# TOP.net
KiCad netlist of a schematic drawn in Altium Designer
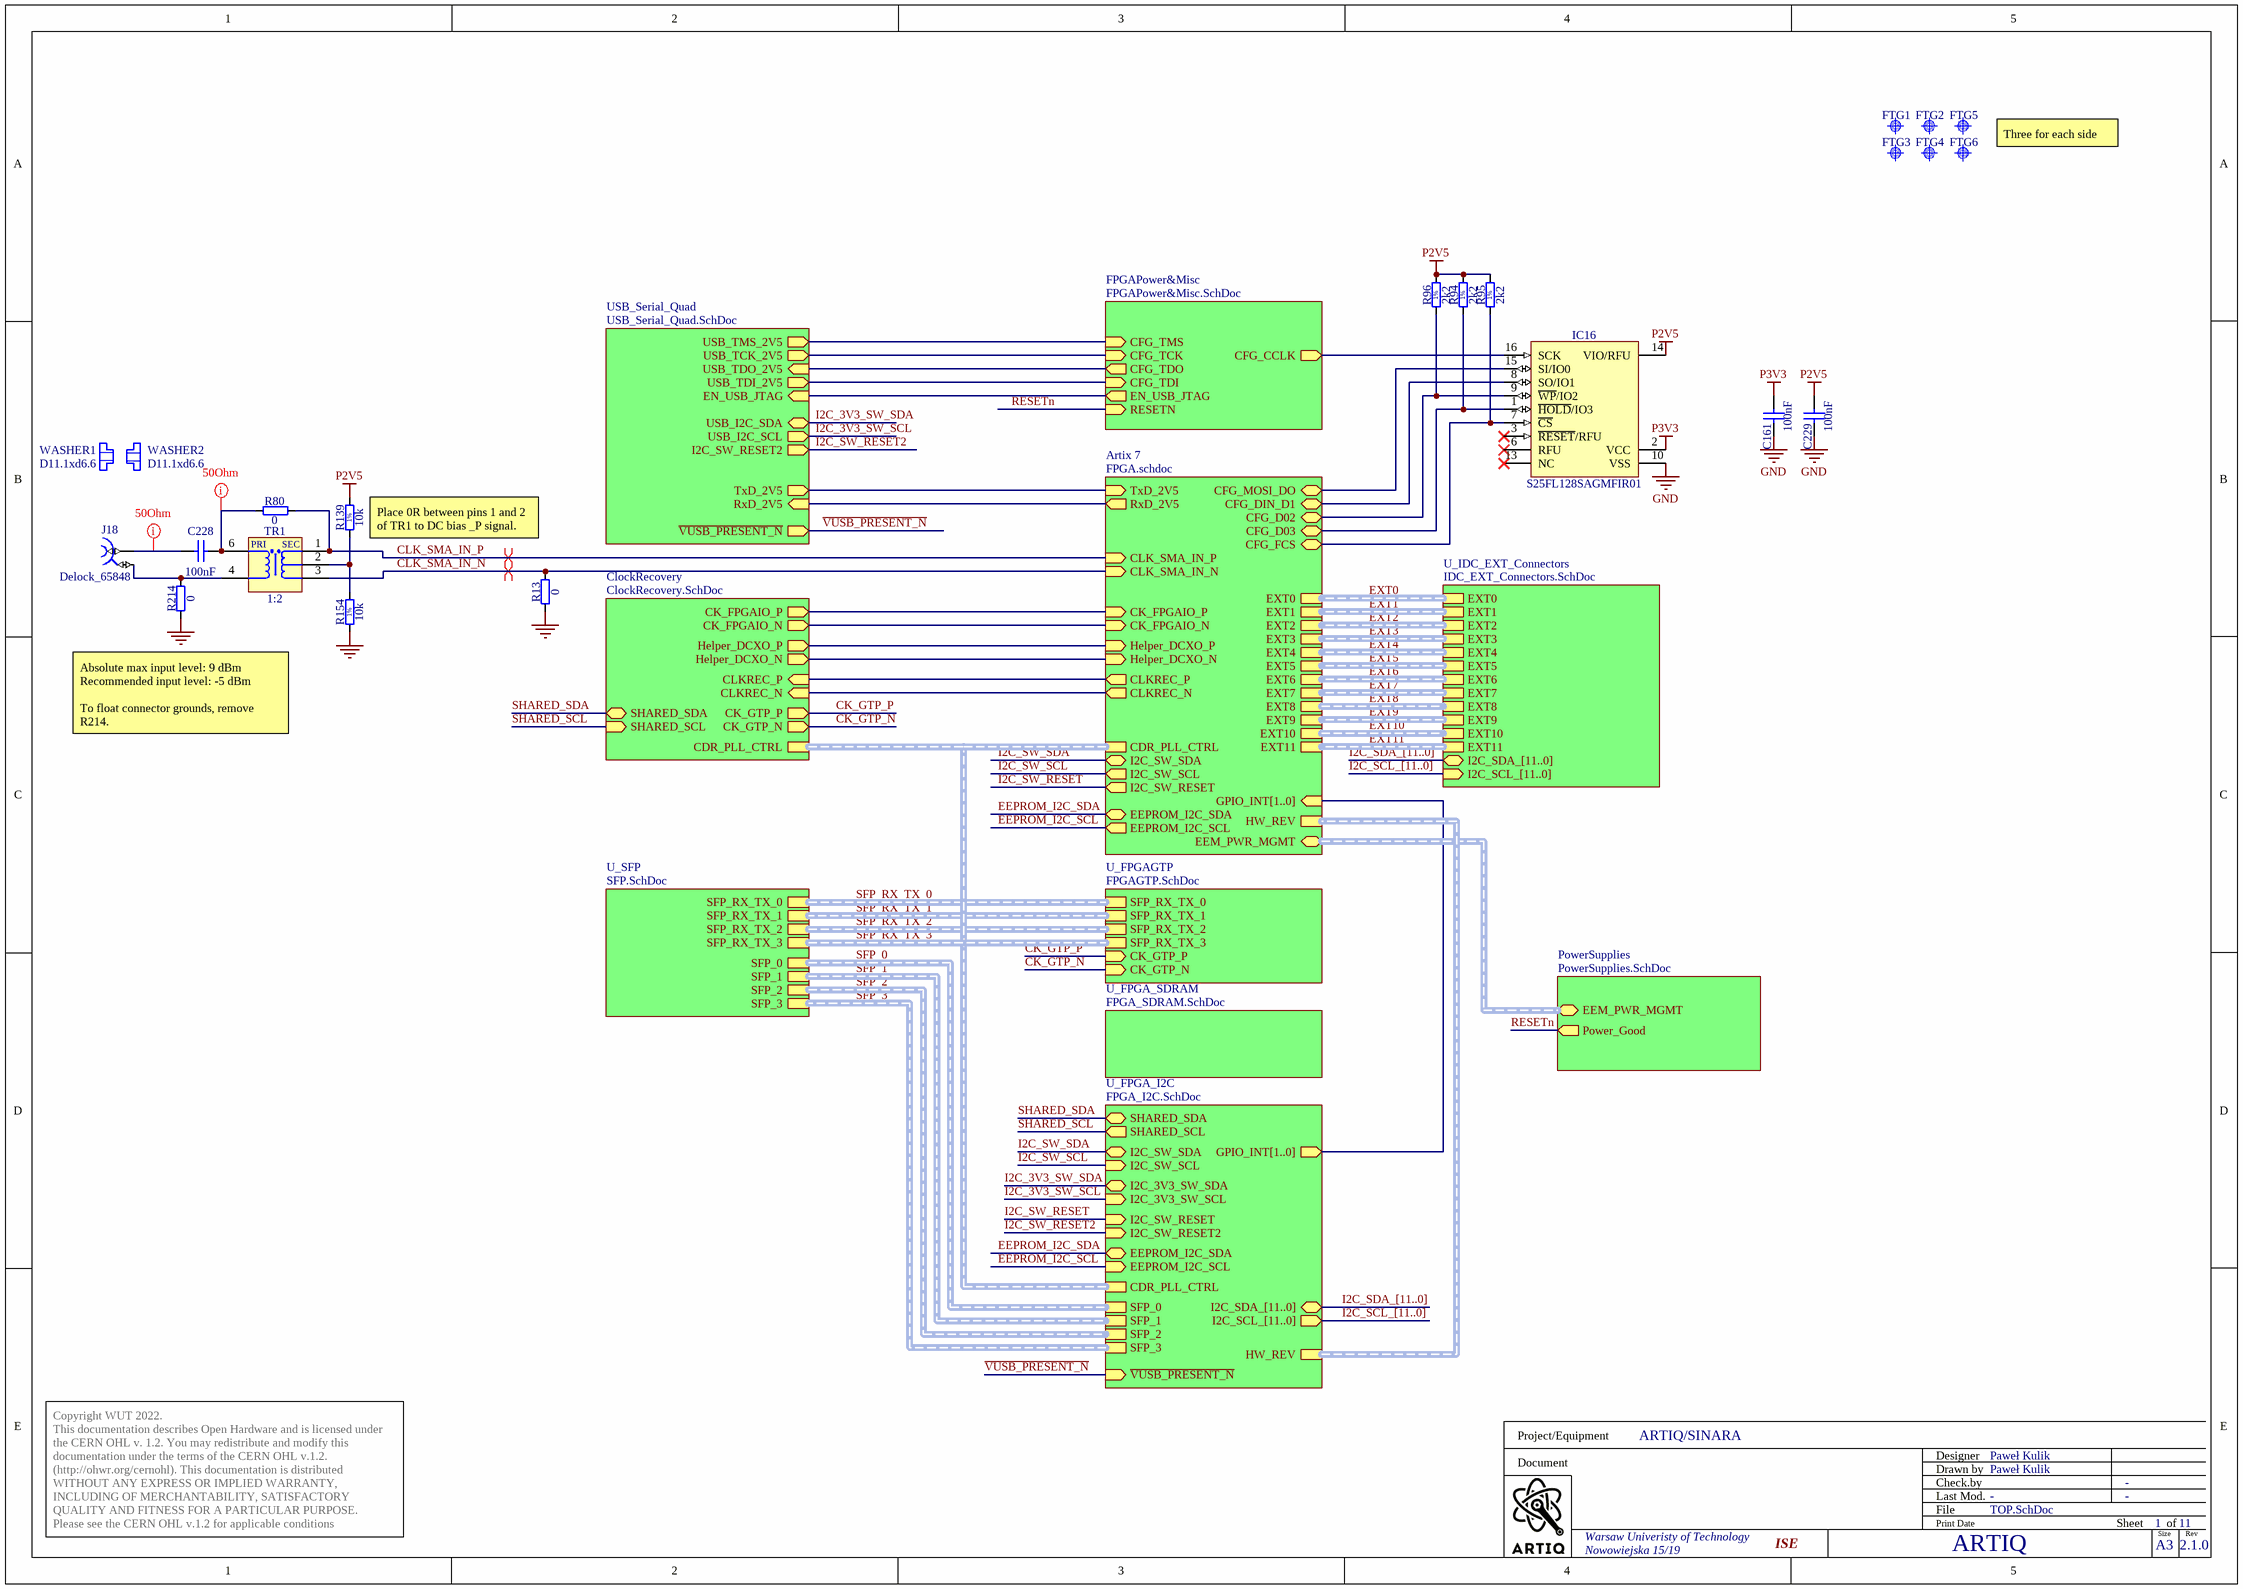
[diagram p0: TOP.SchDoc]

(export (version "E")
  (design (tool "Eeschema 10.0.6"))
  (components
    (comp (ref "C161")
      (value "100nF")
      (footprint "CAPC0603X33N")
      (description "Non-polarised capacitor")
      (fields
        (field (name "PART NUMBER") "CC0201_100NF_6.3V_10%_X5R")
        (field (name "VOLTAGE") "6.3V")
        (field (name "AUTHOR") "CERN DEM JLC")
      )
      (libsource (lib "Capacitors") (part "Capacitor - non polarized"))
    )
    (comp (ref "C228")
      (value "100nF")
      (footprint "CAPC0603X33N")
      (description "Non-polarised capacitor")
      (fields
        (field (name "PART NUMBER") "CC0201_100NF_6.3V_10%_X5R")
        (field (name "VOLTAGE") "6.3V")
        (field (name "AUTHOR") "CERN DEM JLC")
      )
      (libsource (lib "Capacitors") (part "Capacitor - non polarized"))
    )
    (comp (ref "C229")
      (value "100nF")
      (footprint "CAPC0603X33N")
      (description "Non-polarised capacitor")
      (fields
        (field (name "PART NUMBER") "CC0201_100NF_6.3V_10%_X5R")
        (field (name "VOLTAGE") "6.3V")
        (field (name "AUTHOR") "CERN DEM JLC")
      )
      (libsource (lib "Capacitors") (part "Capacitor - non polarized"))
    )
    (comp (ref "FTG1")
      (value "Use only in PCB")
      (footprint "FIDUCIAL_TOP_C100-200")
      (description "Fiducial Target")
      (fields (field (name "PART NUMBER") "FIDUCIAL_TARGET_C100-200") (field (name "AUTHOR") "CERN DEM JLC"))
      (libsource (lib "Eletro-mechanical") (part "Fiducial Target"))
    )
    (comp (ref "FTG2")
      (value "Use only in PCB")
      (footprint "FIDUCIAL_TOP_S100-200")
      (description "Fiducial Target")
      (fields (field (name "PART NUMBER") "FIDUCIAL_TARGET_S100-200") (field (name "AUTHOR") "CERN DEM JLC"))
      (libsource (lib "Eletro-mechanical") (part "Fiducial Target"))
    )
    (comp (ref "FTG3")
      (value "Use only in PCB")
      (footprint "FIDUCIAL_TOP_C100-200")
      (description "Fiducial Target")
      (fields (field (name "PART NUMBER") "FIDUCIAL_TARGET_C100-200") (field (name "AUTHOR") "CERN DEM JLC"))
      (libsource (lib "Eletro-mechanical") (part "Fiducial Target"))
    )
    (comp (ref "FTG4")
      (value "Use only in PCB")
      (footprint "FIDUCIAL_TOP_C100-200")
      (description "Fiducial Target")
      (fields (field (name "PART NUMBER") "FIDUCIAL_TARGET_C100-200") (field (name "AUTHOR") "CERN DEM JLC"))
      (libsource (lib "Eletro-mechanical") (part "Fiducial Target"))
    )
    (comp (ref "FTG5")
      (value "Use only in PCB")
      (footprint "FIDUCIAL_TOP_C100-200")
      (description "Fiducial Target")
      (fields (field (name "PART NUMBER") "FIDUCIAL_TARGET_C100-200") (field (name "AUTHOR") "CERN DEM JLC"))
      (libsource (lib "Eletro-mechanical") (part "Fiducial Target"))
    )
    (comp (ref "FTG6")
      (value "Use only in PCB")
      (footprint "FIDUCIAL_TOP_S100-200")
      (description "Fiducial Target")
      (fields (field (name "PART NUMBER") "FIDUCIAL_TARGET_S100-200") (field (name "AUTHOR") "CERN DEM JLC"))
      (libsource (lib "Eletro-mechanical") (part "Fiducial Target"))
    )
    (comp (ref "IC16")
      (value "S25FL128SAGMFIR01")
      (footprint "SOIC127P1030X265-16N")
      (fields (field (name "MANUFACTURER") "SPANSION") (field (name "AUTHOR") "CERN DEM JLC"))
      (libsource (lib "ICs And Semiconductors") (part "S25FL128SAGMFIR01"))
    )
    (comp (ref "J18")
      (value "Delock_65848")
      (footprint "Delock_65848")
      (description "SMA connector Delock 65848")
      (libsource (lib "TechnoSystem Workspace") (part "Coax_1Female_1Shield"))
    )
    (comp (ref "R13")
      (value "0")
      (footprint "RESC1005X40N")
      (description "Resistor")
      (fields
        (field (name "PART NUMBER") "R0402_0R_JUMPER")
        (field (name "MANUFACTURER") "GENERIC")
        (field (name "AUTHOR") "CERN DEM JLC")
      )
      (libsource (lib "Resistors") (part "Resistor"))
    )
    (comp (ref "R80")
      (value "0")
      (footprint "RESC1005X40N")
      (description "Resistor")
      (fields
        (field (name "PART NUMBER") "R0402_0R_JUMPER")
        (field (name "MANUFACTURER") "GENERIC")
        (field (name "AUTHOR") "CERN DEM JLC")
      )
      (libsource (lib "Resistors") (part "Resistor"))
    )
    (comp (ref "R94")
      (value "2k2")
      (footprint "RESC1005X40N")
      (description "Resistor - 1%")
      (fields
        (field (name "PART NUMBER") "R0402_2K2_1%_0.0625W_100PPM")
        (field (name "POWER") "0.0625W")
        (field (name "AUTHOR") "CERN DEM JLC")
      )
      (libsource (lib "Resistors") (part "Resistor - 1%"))
    )
    (comp (ref "R95")
      (value "2k2")
      (footprint "RESC1005X40N")
      (description "Resistor - 1%")
      (fields
        (field (name "PART NUMBER") "R0402_2K2_1%_0.0625W_100PPM")
        (field (name "POWER") "0.0625W")
        (field (name "AUTHOR") "CERN DEM JLC")
      )
      (libsource (lib "Resistors") (part "Resistor - 1%"))
    )
    (comp (ref "R96")
      (value "2k2")
      (footprint "RESC1005X40N")
      (description "Resistor - 1%")
      (fields
        (field (name "PART NUMBER") "R0402_2K2_1%_0.0625W_100PPM")
        (field (name "POWER") "0.0625W")
        (field (name "AUTHOR") "CERN DEM JLC")
      )
      (libsource (lib "Resistors") (part "Resistor - 1%"))
    )
    (comp (ref "R139")
      (value "10k")
      (footprint "RESC1005X40N")
      (description "Resistor - 1%")
      (fields
        (field (name "PART NUMBER") "R0402_10K_1%_0.0625W_100PPM")
        (field (name "POWER") "0.0625W")
        (field (name "AUTHOR") "CERN DEM JLC")
      )
      (libsource (lib "Resistors") (part "Resistor - 1%"))
    )
    (comp (ref "R154")
      (value "10k")
      (footprint "RESC1005X40N")
      (description "Resistor - 1%")
      (fields
        (field (name "PART NUMBER") "R0402_10K_1%_0.0625W_100PPM")
        (field (name "POWER") "0.0625W")
        (field (name "AUTHOR") "CERN DEM JLC")
      )
      (libsource (lib "Resistors") (part "Resistor - 1%"))
    )
    (comp (ref "R214")
      (value "0")
      (footprint "RESC1005X40N")
      (description "Resistor")
      (fields
        (field (name "PART NUMBER") "R0402_0R_JUMPER")
        (field (name "MANUFACTURER") "GENERIC")
        (field (name "AUTHOR") "CERN DEM JLC")
      )
      (libsource (lib "Resistors") (part "Resistor"))
    )
    (comp (ref "TR1")
      (value "1:2")
      (footprint "XFMR_MINI-CIRCUITS_AT1521")
      (description "50 Ohms 3 to 300MHz RF Transformer")
      (fields
        (field (name "PART NUMBER") "XFMR_MINI-CIRCUITS_TC2-1TX+")
        (field (name "MANUFACTURER") "MINI-CIRCUITS")
        (field (name "AUTHOR") "CERN DEM MR")
      )
      (libsource (lib "Inductors & Transformers") (part "XFMR_MINI-CIRCUITS_TC2-1TX+"))
    )
    (comp (ref "WASHER1")
      (value "D11.1xd6.6")
      (footprint "Keystone_7687")
      (description "SMA_Shoulder Washer")
      (fields
        (field (name "PART NUMBER") "Keystone 7687")
        (field (name "MANUFACTURER") "Keystone")
        (field (name "AUTHOR") "GK")
      )
      (libsource (lib "LIBRARY_SCH") (part "Keystone_7687"))
    )
    (comp (ref "WASHER2")
      (value "D11.1xd6.6")
      (footprint "Keystone_7687")
      (description "SMA_Shoulder Washer")
      (fields
        (field (name "PART NUMBER") "Keystone 7687")
        (field (name "MANUFACTURER") "Keystone")
        (field (name "AUTHOR") "GK")
      )
      (libsource (lib "LIBRARY_SCH") (part "Keystone_7687"))
    )
  )
  (nets
    (net (code "46") (name "/CFG_CCLK") (class "Default")
      (node (ref "IC16") (pin "16") (pinfunction "SCK_16") (pintype "input"))
    )
    (net (code "47") (name "/CFG_D02") (class "Default")
      (node (ref "IC16") (pin "9") (pinfunction "~{WP}/IO2_9") (pintype "bidirectional"))
      (node (ref "R96") (pin "1") (pinfunction "1_1") (pintype "passive"))
    )
    (net (code "48") (name "/CFG_D03") (class "Default")
      (node (ref "IC16") (pin "1") (pinfunction "~{HOLD}/IO3_1") (pintype "bidirectional"))
      (node (ref "R94") (pin "1") (pinfunction "1_1") (pintype "passive"))
    )
    (net (code "49") (name "/CFG_DIN_D1") (class "Default")
      (node (ref "IC16") (pin "8") (pinfunction "SO/IO1_8") (pintype "bidirectional"))
    )
    (net (code "50") (name "/CFG_FCS") (class "Default")
      (node (ref "IC16") (pin "7") (pinfunction "~{CS}_7") (pintype "input"))
      (node (ref "R95") (pin "1") (pinfunction "1_1") (pintype "passive"))
    )
    (net (code "51") (name "/CFG_MOSI_DO") (class "Default")
      (node (ref "IC16") (pin "15") (pinfunction "SI/IO0_15") (pintype "bidirectional"))
    )
    (net (code "59") (name "/CLK_SMA_IN_N") (class "Default")
      (node (ref "R13") (pin "2") (pinfunction "2_2") (pintype "passive"))
      (node (ref "TR1") (pin "3") (pinfunction "S_3") (pintype "passive"))
    )
    (net (code "60") (name "/CLK_SMA_IN_P") (class "Default")
      (node (ref "R80") (pin "2") (pinfunction "2_2") (pintype "passive"))
      (node (ref "TR1") (pin "1") (pinfunction "SDOT_1") (pintype "passive"))
    )
    (net (code "106") (name "GND") (class "Default")
      (node (ref "C161") (pin "1") (pinfunction "1_1") (pintype "passive"))
      (node (ref "C229") (pin "1") (pinfunction "1_1") (pintype "passive"))
      (node (ref "IC16") (pin "10") (pinfunction "VSS_10") (pintype "power_in"))
      (node (ref "R13") (pin "1") (pinfunction "1_1") (pintype "passive"))
      (node (ref "R154") (pin "2") (pinfunction "2_2") (pintype "passive"))
      (node (ref "R214") (pin "1") (pinfunction "1_1") (pintype "passive"))
    )
    (net (code "107") (name "Net-(C228-Pad1)") (class "Default")
      (node (ref "C228") (pin "1") (pinfunction "1_1") (pintype "passive"))
      (node (ref "J18") (pin "1") (pinfunction "1_1") (pintype "bidirectional"))
    )
    (net (code "108") (name "Net-(TR1-NC)") (class "Default")
      (node (ref "R139") (pin "2") (pinfunction "2_2") (pintype "passive"))
      (node (ref "R154") (pin "1") (pinfunction "1_1") (pintype "passive"))
      (node (ref "TR1") (pin "2") (pinfunction "NC_2") (pintype "passive"))
    )
    (net (code "109") (name "Net-(TR1-P)") (class "Default")
      (node (ref "J18") (pin "2") (pinfunction "2_2") (pintype "bidirectional"))
      (node (ref "R214") (pin "2") (pinfunction "2_2") (pintype "passive"))
      (node (ref "TR1") (pin "4") (pinfunction "P_4") (pintype "passive"))
    )
    (net (code "110") (name "Net-(TR1-PDOT)") (class "Default")
      (node (ref "C228") (pin "2") (pinfunction "2_2") (pintype "passive"))
      (node (ref "R80") (pin "1") (pinfunction "1_1") (pintype "passive"))
      (node (ref "TR1") (pin "6") (pinfunction "PDOT_6") (pintype "passive"))
    )
    (net (code "111") (name "P2V5") (class "Default")
      (node (ref "C229") (pin "2") (pinfunction "2_2") (pintype "passive"))
      (node (ref "IC16") (pin "14") (pinfunction "VIO/RFU_14") (pintype "power_in"))
      (node (ref "R139") (pin "1") (pinfunction "1_1") (pintype "passive"))
      (node (ref "R94") (pin "2") (pinfunction "2_2") (pintype "passive"))
      (node (ref "R95") (pin "2") (pinfunction "2_2") (pintype "passive"))
      (node (ref "R96") (pin "2") (pinfunction "2_2") (pintype "passive"))
    )
    (net (code "112") (name "P3V3") (class "Default")
      (node (ref "C161") (pin "2") (pinfunction "2_2") (pintype "passive"))
      (node (ref "IC16") (pin "2") (pinfunction "VCC_2") (pintype "power_in"))
    )
    (net (code "113") (name "unconnected-(IC16-NC-Pad13)") (class "Default")
      (node (ref "IC16") (pin "13") (pinfunction "NC_13") (pintype "passive+no_connect"))
    )
    (net (code "114") (name "unconnected-(IC16-RFU-Pad6)") (class "Default")
      (node (ref "IC16") (pin "6") (pinfunction "RFU_6") (pintype "passive+no_connect"))
    )
    (net (code "115") (name "unconnected-(IC16-~{RESET}{slash}RFU-Pad3)") (class "Default")
      (node (ref "IC16") (pin "3") (pinfunction "~{RESET}/RFU_3") (pintype "input+no_connect"))
    )
  )
)
